# Transmitter.net
KiCad netlist of a schematic drawn in Altium Designer
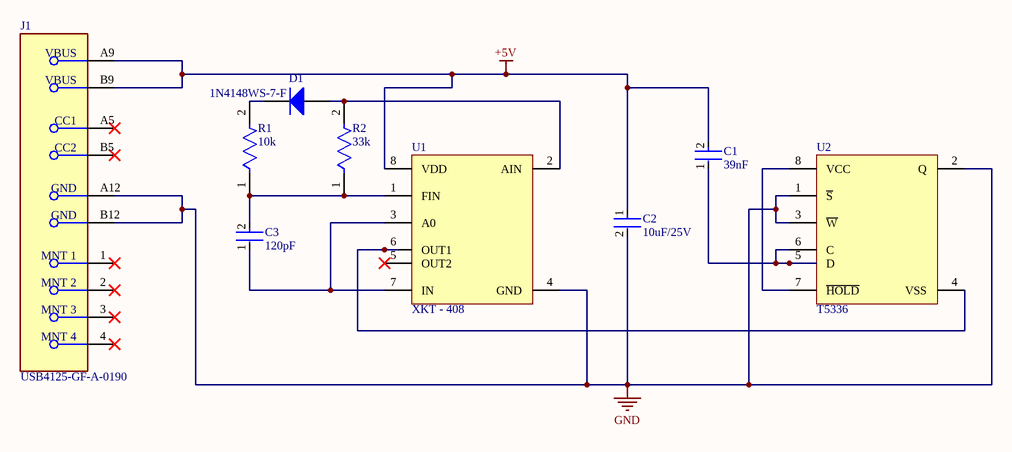
[diagram p0: Transmitter.SchDoc]

(export (version "E")
  (design (tool "Eeschema 10.0.6"))
  (components
    (comp (ref "C1")
      (value "39nF")
      (footprint "FP-GRM15-MFG")
      (description "CAP CER 0.1UF 16V X7R 0402")
      (fields (field (name "MANUFACTURER PART NUMBER") "GRM155R71C104KA88D") (field (name "TOLERANCE") "10%"))
      (libsource (lib "Altium Content Vault") (part "236180d848d6139a670b325ea6854c9"))
    )
    (comp (ref "C2")
      (value "10uF/25V")
      (footprint "FP-0603-L_1_6_0_15-W_0_81-IPC_A")
      (description "General Purpose Ceramic Capacitor, 0603, 1nF, 10%, X7R, 15%, 50V")
      (fields (field (name "VOLTAGE") "50V") (field (name "TOLERANCE") "10%"))
      (libsource (lib "Altium Content Vault") (part "02cd4be3c70576c341d710602a673aa"))
    )
    (comp (ref "C3")
      (value "120pF")
      (footprint "FP-GRM15-MFG")
      (description "CAP CER 0.1UF 16V X7R 0402")
      (fields (field (name "MANUFACTURER PART NUMBER") "GRM155R71C104KA88D") (field (name "TOLERANCE") "10%"))
      (libsource (lib "Altium Content Vault") (part "236180d848d6139a670b325ea6854c9"))
    )
    (comp (ref "D1")
      (value "1N4148WS-7-F")
      (footprint "DIOD-SOD323-2-A_V")
      (description "Fast Switching Diode, 75 V, 0.3 A, -65 to 150 degC, 2-Pin SOD323, RoHS, Tape and Reel")
      (libsource (lib "Altium Content Vault") (part "D-AK-2"))
    )
    (comp (ref "J1")
      (value "USB4125-GF-A-0190")
      (footprint "FP-USB4125-GF-A-0190-MFG")
      (description "CONN RCPT TYPE C 6P SMD RA")
      (libsource (lib "Altium Content Vault") (part "a055484d46e58b234844902c9fd883a"))
    )
    (comp (ref "R1")
      (value "10k")
      (footprint "FP-ERJ2RK-IPC_A")
      (description "RES SMD 150 OHM 1% 1/10W 0402")
      (fields (field (name "TOLERANCE") "1%"))
      (libsource (lib "Altium Content Vault") (part "1029c3af85768c4190bb7ad29bc67b5"))
    )
    (comp (ref "R2")
      (value "33k")
      (footprint "FP-ERJ2RK-IPC_A")
      (description "RES SMD 150 OHM 1% 1/10W 0402")
      (fields (field (name "TOLERANCE") "1%"))
      (libsource (lib "Altium Content Vault") (part "1029c3af85768c4190bb7ad29bc67b5"))
    )
    (comp (ref "U1")
      (value "XKT - 408")
      (footprint "SOP127P600X173-8_PRSP0008DF-B_N")
      (description "Serial Peripheral Interface 32k EEPROM (4-kword × 8-bit) 64k EEPROM (8-kword × 8-bit)")
      (libsource (lib "Altium Content Vault") (part "f4225b3ad442a44c874fac446cf76bb"))
    )
    (comp (ref "U2")
      (value "T5336")
      (footprint "SOP127P600X173-8_PRSP0008DF-B_N")
      (description "Serial Peripheral Interface 32k EEPROM (4-kword × 8-bit) 64k EEPROM (8-kword × 8-bit)")
      (libsource (lib "Altium Content Vault") (part "f4225b3ad442a44c874fac446cf76bb"))
    )
  )
  (nets
    (net (code "1") (name "+5V") (class "Default")
      (node (ref "C1") (pin "2") (pinfunction "2_2") (pintype "passive"))
      (node (ref "C2") (pin "1") (pinfunction "1_1") (pintype "passive"))
      (node (ref "J1") (pin "A9") (pinfunction "VBUS_A9") (pintype "passive"))
      (node (ref "J1") (pin "B9") (pinfunction "VBUS_B9") (pintype "passive"))
      (node (ref "U1") (pin "8") (pinfunction "VCC_8") (pintype "power_in"))
    )
    (net (code "2") (name "GND") (class "Default")
      (node (ref "C2") (pin "2") (pinfunction "2_2") (pintype "passive"))
      (node (ref "J1") (pin "A12") (pinfunction "GND_A12") (pintype "passive"))
      (node (ref "J1") (pin "B12") (pinfunction "GND_B12") (pintype "passive"))
      (node (ref "U1") (pin "4") (pinfunction "VSS_4") (pintype "power_in"))
      (node (ref "U2") (pin "1") (pinfunction "~{S}_1") (pintype "passive"))
      (node (ref "U2") (pin "2") (pinfunction "Q_2") (pintype "power_in"))
      (node (ref "U2") (pin "3") (pinfunction "~{W}_3") (pintype "passive"))
    )
    (net (code "3") (name "Net-(D1-A)") (class "Default")
      (node (ref "D1") (pin "1") (pinfunction "A_1") (pintype "passive"))
      (node (ref "R2") (pin "2") (pinfunction "2_2") (pintype "passive"))
      (node (ref "U1") (pin "2") (pinfunction "Q_2") (pintype "power_in"))
    )
    (net (code "4") (name "Net-(D1-K)") (class "Default")
      (node (ref "D1") (pin "2") (pinfunction "K_2") (pintype "passive"))
      (node (ref "R1") (pin "2") (pinfunction "2_2") (pintype "passive"))
    )
    (net (code "5") (name "Net-(U1-C)") (class "Default")
      (node (ref "U1") (pin "6") (pinfunction "C_6") (pintype "passive"))
      (node (ref "U2") (pin "4") (pinfunction "VSS_4") (pintype "power_in"))
    )
    (net (code "6") (name "Net-(U1-~{HOLD})") (class "Default")
      (node (ref "C3") (pin "1") (pinfunction "1_1") (pintype "passive"))
      (node (ref "U1") (pin "3") (pinfunction "~{W}_3") (pintype "passive"))
      (node (ref "U1") (pin "7") (pinfunction "~{HOLD}_7") (pintype "passive"))
    )
    (net (code "7") (name "Net-(U1-~{S})") (class "Default")
      (node (ref "C3") (pin "2") (pinfunction "2_2") (pintype "passive"))
      (node (ref "R1") (pin "1") (pinfunction "1_1") (pintype "passive"))
      (node (ref "R2") (pin "1") (pinfunction "1_1") (pintype "passive"))
      (node (ref "U1") (pin "1") (pinfunction "~{S}_1") (pintype "passive"))
    )
    (net (code "8") (name "Net-(U2-C)") (class "Default")
      (node (ref "C1") (pin "1") (pinfunction "1_1") (pintype "passive"))
      (node (ref "U2") (pin "5") (pinfunction "D_5") (pintype "passive"))
      (node (ref "U2") (pin "6") (pinfunction "C_6") (pintype "passive"))
    )
    (net (code "9") (name "Net-(U2-VCC)") (class "Default")
      (node (ref "U2") (pin "7") (pinfunction "~{HOLD}_7") (pintype "passive"))
      (node (ref "U2") (pin "8") (pinfunction "VCC_8") (pintype "power_in"))
    )
    (net (code "10") (name "unconnected-(J1-CC1-PadA5)") (class "Default")
      (node (ref "J1") (pin "A5") (pinfunction "CC1_A5") (pintype "passive+no_connect"))
    )
    (net (code "11") (name "unconnected-(J1-CC2-PadB5)") (class "Default")
      (node (ref "J1") (pin "B5") (pinfunction "CC2_B5") (pintype "passive+no_connect"))
    )
    (net (code "12") (name "unconnected-(J1-MNT_1-Pad1)") (class "Default")
      (node (ref "J1") (pin "1") (pinfunction "MNT_1_1") (pintype "passive+no_connect"))
    )
    (net (code "13") (name "unconnected-(J1-MNT_2-Pad2)") (class "Default")
      (node (ref "J1") (pin "2") (pinfunction "MNT_2_2") (pintype "passive+no_connect"))
    )
    (net (code "14") (name "unconnected-(J1-MNT_3-Pad3)") (class "Default")
      (node (ref "J1") (pin "3") (pinfunction "MNT_3_3") (pintype "passive+no_connect"))
    )
    (net (code "15") (name "unconnected-(J1-MNT_4-Pad4)") (class "Default")
      (node (ref "J1") (pin "4") (pinfunction "MNT_4_4") (pintype "passive+no_connect"))
    )
    (net (code "16") (name "unconnected-(U1-D-Pad5)") (class "Default")
      (node (ref "U1") (pin "5") (pinfunction "D_5") (pintype "passive+no_connect"))
    )
  )
)
